# io.net
KiCad netlist of a schematic drawn in EAGLE
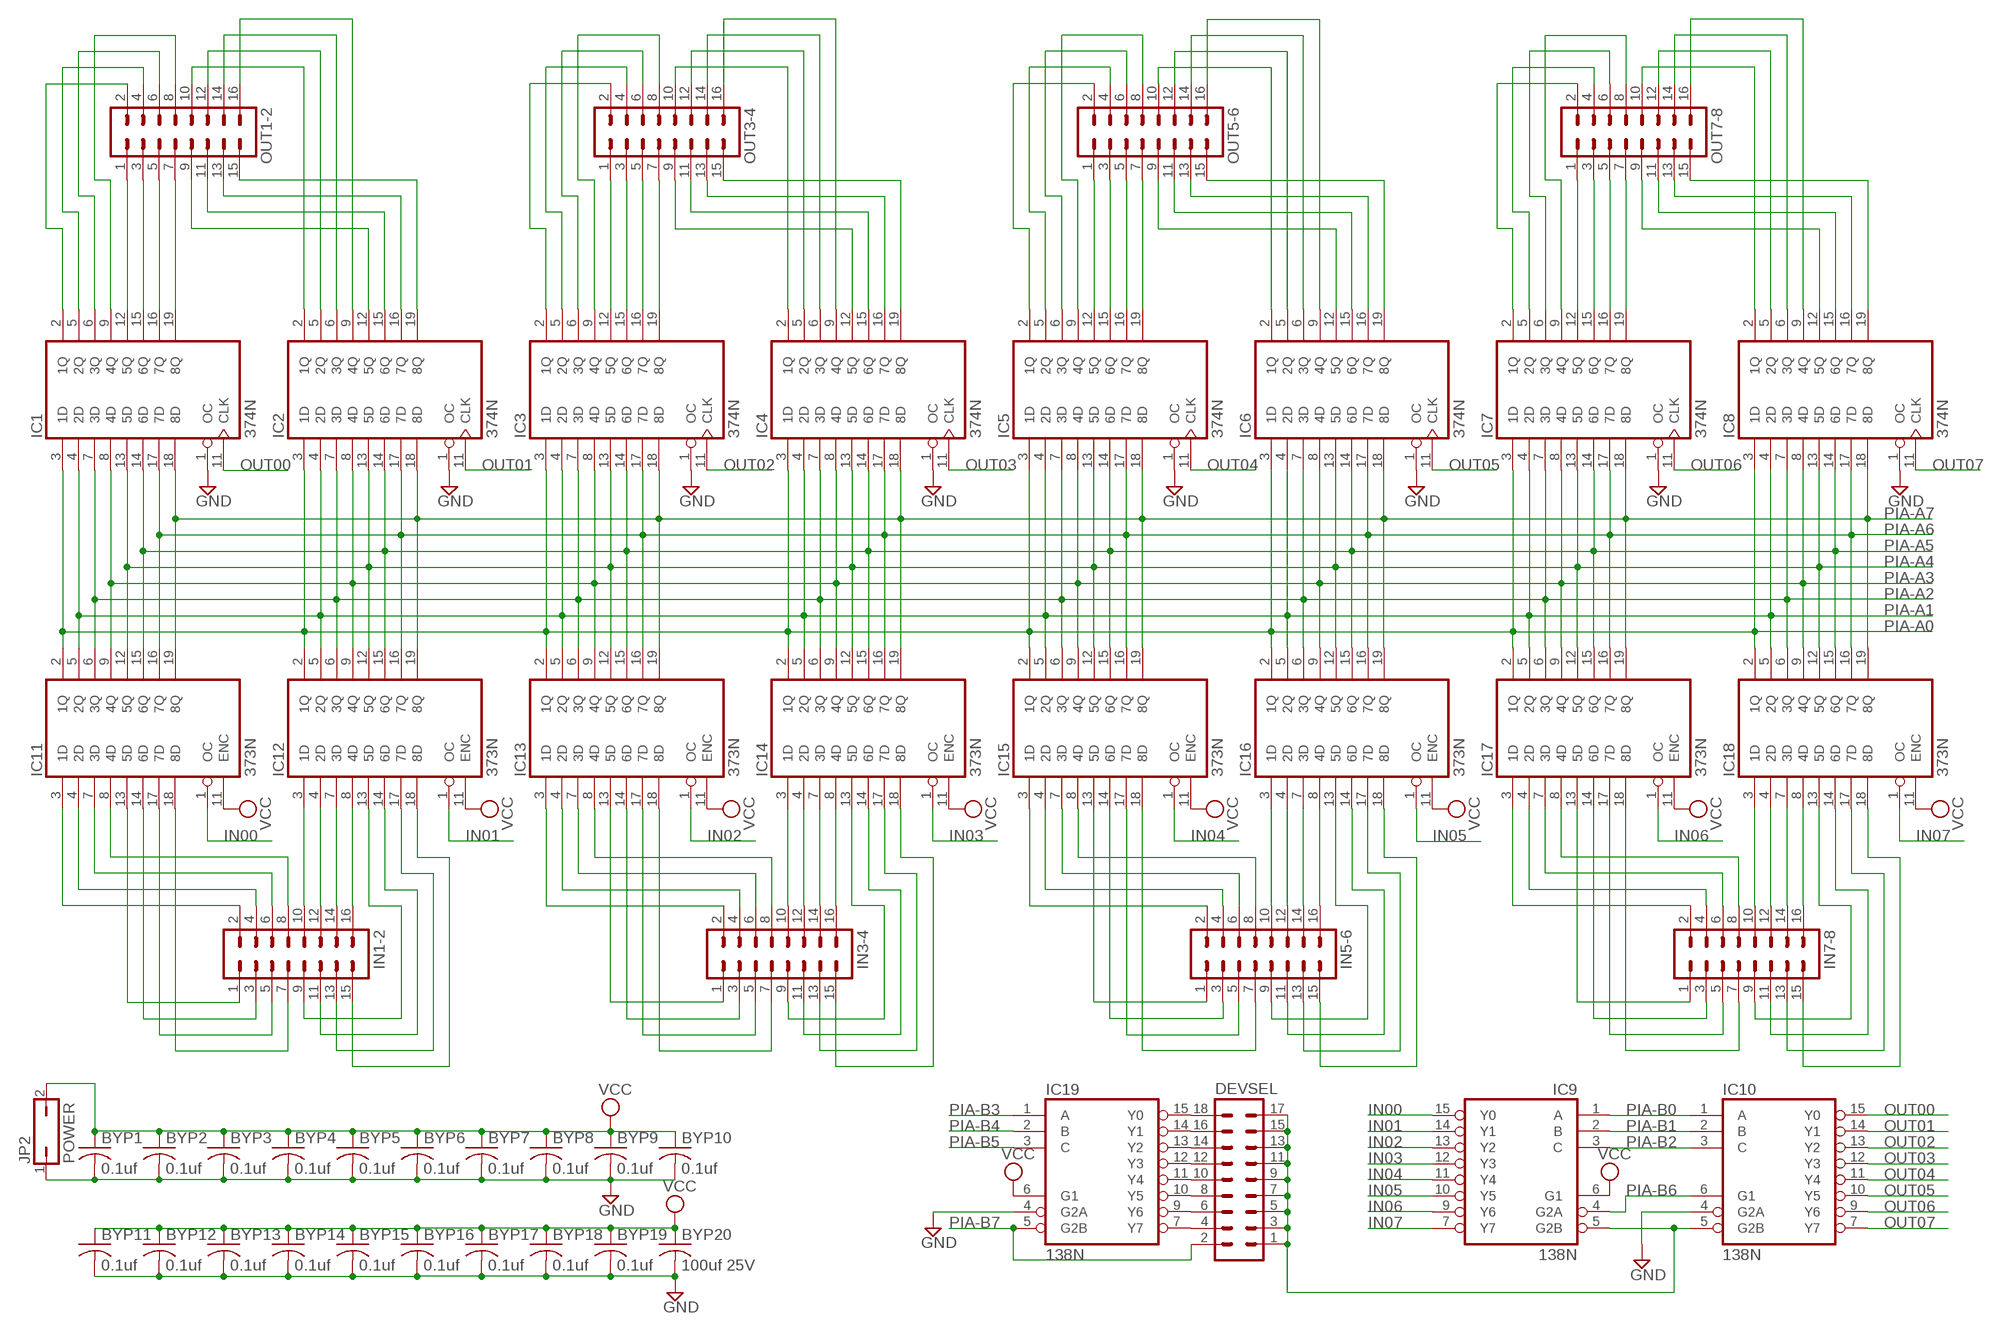
[diagram p0: schematic, sheet 1]
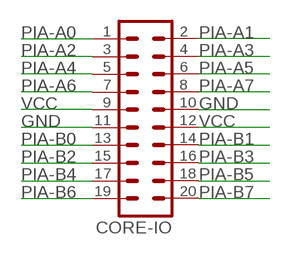
[diagram p1: schematic, sheet 2]

(export (version "E")
  (design (tool "Eeschema 10.0.6"))
  (components
    (comp (ref "BYP1")
      (value "0.1uf")
      (footprint "eagle-import:C050-025X075")
      (libsource (lib "eagle-import") (part "C-US050-025X075"))
    )
    (comp (ref "BYP2")
      (value "0.1uf")
      (footprint "eagle-import:C050-025X075")
      (libsource (lib "eagle-import") (part "C-US050-025X075"))
    )
    (comp (ref "BYP3")
      (value "0.1uf")
      (footprint "eagle-import:C050-025X075")
      (libsource (lib "eagle-import") (part "C-US050-025X075"))
    )
    (comp (ref "BYP4")
      (value "0.1uf")
      (footprint "eagle-import:C050-025X075")
      (libsource (lib "eagle-import") (part "C-US050-025X075"))
    )
    (comp (ref "BYP5")
      (value "0.1uf")
      (footprint "eagle-import:C050-025X075")
      (libsource (lib "eagle-import") (part "C-US050-025X075"))
    )
    (comp (ref "BYP6")
      (value "0.1uf")
      (footprint "eagle-import:C050-025X075")
      (libsource (lib "eagle-import") (part "C-US050-025X075"))
    )
    (comp (ref "BYP7")
      (value "0.1uf")
      (footprint "eagle-import:C050-025X075")
      (libsource (lib "eagle-import") (part "C-US050-025X075"))
    )
    (comp (ref "BYP8")
      (value "0.1uf")
      (footprint "eagle-import:C050-025X075")
      (libsource (lib "eagle-import") (part "C-US050-025X075"))
    )
    (comp (ref "BYP9")
      (value "0.1uf")
      (footprint "eagle-import:C050-025X075")
      (libsource (lib "eagle-import") (part "C-US050-025X075"))
    )
    (comp (ref "BYP10")
      (value "0.1uf")
      (footprint "eagle-import:C050-025X075")
      (libsource (lib "eagle-import") (part "C-US050-025X075"))
    )
    (comp (ref "BYP11")
      (value "0.1uf")
      (footprint "eagle-import:C050-025X075")
      (libsource (lib "eagle-import") (part "C-US050-025X075"))
    )
    (comp (ref "BYP12")
      (value "0.1uf")
      (footprint "eagle-import:C050-025X075")
      (libsource (lib "eagle-import") (part "C-US050-025X075"))
    )
    (comp (ref "BYP13")
      (value "0.1uf")
      (footprint "eagle-import:C050-025X075")
      (libsource (lib "eagle-import") (part "C-US050-025X075"))
    )
    (comp (ref "BYP14")
      (value "0.1uf")
      (footprint "eagle-import:C050-025X075")
      (libsource (lib "eagle-import") (part "C-US050-025X075"))
    )
    (comp (ref "BYP15")
      (value "0.1uf")
      (footprint "eagle-import:C050-025X075")
      (libsource (lib "eagle-import") (part "C-US050-025X075"))
    )
    (comp (ref "BYP16")
      (value "0.1uf")
      (footprint "eagle-import:C050-025X075")
      (libsource (lib "eagle-import") (part "C-US050-025X075"))
    )
    (comp (ref "BYP17")
      (value "0.1uf")
      (footprint "eagle-import:C050-025X075")
      (libsource (lib "eagle-import") (part "C-US050-025X075"))
    )
    (comp (ref "BYP18")
      (value "0.1uf")
      (footprint "eagle-import:C050-025X075")
      (libsource (lib "eagle-import") (part "C-US050-025X075"))
    )
    (comp (ref "BYP19")
      (value "0.1uf")
      (footprint "eagle-import:C050-025X075")
      (libsource (lib "eagle-import") (part "C-US050-025X075"))
    )
    (comp (ref "BYP20")
      (value "100uf 25V")
      (footprint "eagle-import:C150-064X183")
      (libsource (lib "eagle-import") (part "C-US150-064X183"))
    )
    (comp (ref "DEVSEL")
      (value "MA09-2")
      (footprint "eagle-import:MA09-2")
      (libsource (lib "eagle-import") (part "MA09-2"))
    )
    (comp (ref "IC1")
      (value "374N")
      (footprint "eagle-import:DIL20")
      (libsource (lib "eagle-import") (part "74374NLS"))
    )
    (comp (ref "IC2")
      (value "374N")
      (footprint "eagle-import:DIL20")
      (libsource (lib "eagle-import") (part "74374NLS"))
    )
    (comp (ref "IC3")
      (value "374N")
      (footprint "eagle-import:DIL20")
      (libsource (lib "eagle-import") (part "74374NLS"))
    )
    (comp (ref "IC4")
      (value "374N")
      (footprint "eagle-import:DIL20")
      (libsource (lib "eagle-import") (part "74374NLS"))
    )
    (comp (ref "IC5")
      (value "374N")
      (footprint "eagle-import:DIL20")
      (libsource (lib "eagle-import") (part "74374NLS"))
    )
    (comp (ref "IC6")
      (value "374N")
      (footprint "eagle-import:DIL20")
      (libsource (lib "eagle-import") (part "74374NLS"))
    )
    (comp (ref "IC7")
      (value "374N")
      (footprint "eagle-import:DIL20")
      (libsource (lib "eagle-import") (part "74374NLS"))
    )
    (comp (ref "IC8")
      (value "374N")
      (footprint "eagle-import:DIL20")
      (libsource (lib "eagle-import") (part "74374NLS"))
    )
    (comp (ref "IC9")
      (value "138N")
      (footprint "eagle-import:DIL16")
      (libsource (lib "eagle-import") (part "74138NLS"))
    )
    (comp (ref "IC10")
      (value "138N")
      (footprint "eagle-import:DIL16")
      (libsource (lib "eagle-import") (part "74138NLS"))
    )
    (comp (ref "IC11")
      (value "373N")
      (footprint "eagle-import:DIL20")
      (libsource (lib "eagle-import") (part "74373NLS"))
    )
    (comp (ref "IC12")
      (value "373N")
      (footprint "eagle-import:DIL20")
      (libsource (lib "eagle-import") (part "74373NLS"))
    )
    (comp (ref "IC13")
      (value "373N")
      (footprint "eagle-import:DIL20")
      (libsource (lib "eagle-import") (part "74373NLS"))
    )
    (comp (ref "IC14")
      (value "373N")
      (footprint "eagle-import:DIL20")
      (libsource (lib "eagle-import") (part "74373NLS"))
    )
    (comp (ref "IC15")
      (value "373N")
      (footprint "eagle-import:DIL20")
      (libsource (lib "eagle-import") (part "74373NLS"))
    )
    (comp (ref "IC16")
      (value "373N")
      (footprint "eagle-import:DIL20")
      (libsource (lib "eagle-import") (part "74373NLS"))
    )
    (comp (ref "IC17")
      (value "373N")
      (footprint "eagle-import:DIL20")
      (libsource (lib "eagle-import") (part "74373NLS"))
    )
    (comp (ref "IC18")
      (value "373N")
      (footprint "eagle-import:DIL20")
      (libsource (lib "eagle-import") (part "74373NLS"))
    )
    (comp (ref "IC19")
      (value "138N")
      (footprint "eagle-import:DIL16")
      (libsource (lib "eagle-import") (part "74138NLS"))
    )
    (comp (ref "IN1-2")
      (value "MA08-2")
      (footprint "eagle-import:MA08-2")
      (libsource (lib "eagle-import") (part "MA08-2"))
    )
    (comp (ref "IN3-4")
      (value "MA08-2")
      (footprint "eagle-import:MA08-2")
      (libsource (lib "eagle-import") (part "MA08-2"))
    )
    (comp (ref "IN5-6")
      (value "MA08-2")
      (footprint "eagle-import:MA08-2")
      (libsource (lib "eagle-import") (part "MA08-2"))
    )
    (comp (ref "IN7-8")
      (value "MA08-2")
      (footprint "eagle-import:MA08-2")
      (libsource (lib "eagle-import") (part "MA08-2"))
    )
    (comp (ref "JP2")
      (value "POWER")
      (footprint "eagle-import:JP1")
      (libsource (lib "eagle-import") (part "JP1Q"))
    )
    (comp (ref "OUT1-2")
      (value "MA08-2")
      (footprint "eagle-import:MA08-2")
      (libsource (lib "eagle-import") (part "MA08-2"))
    )
    (comp (ref "OUT3-4")
      (value "MA08-2")
      (footprint "eagle-import:MA08-2")
      (libsource (lib "eagle-import") (part "MA08-2"))
    )
    (comp (ref "OUT5-6")
      (value "MA08-2")
      (footprint "eagle-import:MA08-2")
      (libsource (lib "eagle-import") (part "MA08-2"))
    )
    (comp (ref "OUT7-8")
      (value "MA08-2")
      (footprint "eagle-import:MA08-2")
      (libsource (lib "eagle-import") (part "MA08-2"))
    )
    (comp (ref "CORE-IO")
      (value "MA10-2")
      (footprint "eagle-import:MA10-2")
      (libsource (lib "eagle-import") (part "MA10-2"))
    )
  )
  (nets
    (net (code "1") (name "GND") (class "Default")
      (node (ref "BYP1") (pin "2") (pinfunction "2_2") (pintype "passive"))
      (node (ref "BYP10") (pin "2") (pinfunction "2_2") (pintype "passive"))
      (node (ref "BYP11") (pin "2") (pinfunction "2_2") (pintype "passive"))
      (node (ref "BYP12") (pin "2") (pinfunction "2_2") (pintype "passive"))
      (node (ref "BYP13") (pin "2") (pinfunction "2_2") (pintype "passive"))
      (node (ref "BYP14") (pin "2") (pinfunction "2_2") (pintype "passive"))
      (node (ref "BYP15") (pin "2") (pinfunction "2_2") (pintype "passive"))
      (node (ref "BYP16") (pin "2") (pinfunction "2_2") (pintype "passive"))
      (node (ref "BYP17") (pin "2") (pinfunction "2_2") (pintype "passive"))
      (node (ref "BYP18") (pin "2") (pinfunction "2_2") (pintype "passive"))
      (node (ref "BYP19") (pin "2") (pinfunction "2_2") (pintype "passive"))
      (node (ref "BYP2") (pin "2") (pinfunction "2_2") (pintype "passive"))
      (node (ref "BYP20") (pin "2") (pinfunction "2_2") (pintype "passive"))
      (node (ref "BYP3") (pin "2") (pinfunction "2_2") (pintype "passive"))
      (node (ref "BYP4") (pin "2") (pinfunction "2_2") (pintype "passive"))
      (node (ref "BYP5") (pin "2") (pinfunction "2_2") (pintype "passive"))
      (node (ref "BYP6") (pin "2") (pinfunction "2_2") (pintype "passive"))
      (node (ref "BYP7") (pin "2") (pinfunction "2_2") (pintype "passive"))
      (node (ref "BYP8") (pin "2") (pinfunction "2_2") (pintype "passive"))
      (node (ref "BYP9") (pin "2") (pinfunction "2_2") (pintype "passive"))
      (node (ref "CORE-IO") (pin "10") (pinfunction "10_10") (pintype "passive"))
      (node (ref "CORE-IO") (pin "11") (pinfunction "11_11") (pintype "passive"))
      (node (ref "IC1") (pin "1") (pinfunction "OC_1") (pintype "input"))
      (node (ref "IC10") (pin "4") (pinfunction "G2A_4") (pintype "input"))
      (node (ref "IC19") (pin "4") (pinfunction "G2A_4") (pintype "input"))
      (node (ref "IC2") (pin "1") (pinfunction "OC_1") (pintype "input"))
      (node (ref "IC3") (pin "1") (pinfunction "OC_1") (pintype "input"))
      (node (ref "IC4") (pin "1") (pinfunction "OC_1") (pintype "input"))
      (node (ref "IC5") (pin "1") (pinfunction "OC_1") (pintype "input"))
      (node (ref "IC6") (pin "1") (pinfunction "OC_1") (pintype "input"))
      (node (ref "IC7") (pin "1") (pinfunction "OC_1") (pintype "input"))
      (node (ref "IC8") (pin "1") (pinfunction "OC_1") (pintype "input"))
      (node (ref "JP2") (pin "1") (pinfunction "1_1") (pintype "passive"))
    )
    (net (code "2") (name "IN00") (class "Default")
      (node (ref "IC11") (pin "1") (pinfunction "OC_1") (pintype "input"))
      (node (ref "IC9") (pin "15") (pinfunction "Y0_15") (pintype "output"))
    )
    (net (code "3") (name "IN01") (class "Default")
      (node (ref "IC12") (pin "1") (pinfunction "OC_1") (pintype "input"))
      (node (ref "IC9") (pin "14") (pinfunction "Y1_14") (pintype "output"))
    )
    (net (code "4") (name "IN02") (class "Default")
      (node (ref "IC13") (pin "1") (pinfunction "OC_1") (pintype "input"))
      (node (ref "IC9") (pin "13") (pinfunction "Y2_13") (pintype "output"))
    )
    (net (code "5") (name "IN03") (class "Default")
      (node (ref "IC14") (pin "1") (pinfunction "OC_1") (pintype "input"))
      (node (ref "IC9") (pin "12") (pinfunction "Y3_12") (pintype "output"))
    )
    (net (code "6") (name "IN04") (class "Default")
      (node (ref "IC15") (pin "1") (pinfunction "OC_1") (pintype "input"))
      (node (ref "IC9") (pin "11") (pinfunction "Y4_11") (pintype "output"))
    )
    (net (code "7") (name "IN05") (class "Default")
      (node (ref "IC16") (pin "1") (pinfunction "OC_1") (pintype "input"))
      (node (ref "IC9") (pin "10") (pinfunction "Y5_10") (pintype "output"))
    )
    (net (code "8") (name "IN06") (class "Default")
      (node (ref "IC17") (pin "1") (pinfunction "OC_1") (pintype "input"))
      (node (ref "IC9") (pin "9") (pinfunction "Y6_9") (pintype "output"))
    )
    (net (code "9") (name "IN07") (class "Default")
      (node (ref "IC18") (pin "1") (pinfunction "OC_1") (pintype "input"))
      (node (ref "IC9") (pin "7") (pinfunction "Y7_7") (pintype "output"))
    )
    (net (code "10") (name "Net-(IC1A-1Q)") (class "Default")
      (node (ref "IC1") (pin "2") (pinfunction "1Q_2") (pintype "tri_state"))
      (node (ref "OUT1-2") (pin "2") (pinfunction "2_2") (pintype "passive"))
    )
    (net (code "11") (name "Net-(IC1A-2Q)") (class "Default")
      (node (ref "IC1") (pin "5") (pinfunction "2Q_5") (pintype "tri_state"))
      (node (ref "OUT1-2") (pin "4") (pinfunction "4_4") (pintype "passive"))
    )
    (net (code "12") (name "Net-(IC1A-3Q)") (class "Default")
      (node (ref "IC1") (pin "6") (pinfunction "3Q_6") (pintype "tri_state"))
      (node (ref "OUT1-2") (pin "6") (pinfunction "6_6") (pintype "passive"))
    )
    (net (code "13") (name "Net-(IC1A-4Q)") (class "Default")
      (node (ref "IC1") (pin "9") (pinfunction "4Q_9") (pintype "tri_state"))
      (node (ref "OUT1-2") (pin "8") (pinfunction "8_8") (pintype "passive"))
    )
    (net (code "14") (name "Net-(IC1A-5Q)") (class "Default")
      (node (ref "IC1") (pin "12") (pinfunction "5Q_12") (pintype "tri_state"))
      (node (ref "OUT1-2") (pin "1") (pinfunction "1_1") (pintype "passive"))
    )
    (net (code "15") (name "Net-(IC1A-6Q)") (class "Default")
      (node (ref "IC1") (pin "15") (pinfunction "6Q_15") (pintype "tri_state"))
      (node (ref "OUT1-2") (pin "3") (pinfunction "3_3") (pintype "passive"))
    )
    (net (code "16") (name "Net-(IC1A-7Q)") (class "Default")
      (node (ref "IC1") (pin "16") (pinfunction "7Q_16") (pintype "tri_state"))
      (node (ref "OUT1-2") (pin "5") (pinfunction "5_5") (pintype "passive"))
    )
    (net (code "17") (name "Net-(IC1A-8Q)") (class "Default")
      (node (ref "IC1") (pin "19") (pinfunction "8Q_19") (pintype "tri_state"))
      (node (ref "OUT1-2") (pin "7") (pinfunction "7_7") (pintype "passive"))
    )
    (net (code "18") (name "Net-(IC2A-1Q)") (class "Default")
      (node (ref "IC2") (pin "2") (pinfunction "1Q_2") (pintype "tri_state"))
      (node (ref "OUT1-2") (pin "10") (pinfunction "10_10") (pintype "passive"))
    )
    (net (code "19") (name "Net-(IC2A-2Q)") (class "Default")
      (node (ref "IC2") (pin "5") (pinfunction "2Q_5") (pintype "tri_state"))
      (node (ref "OUT1-2") (pin "12") (pinfunction "12_12") (pintype "passive"))
    )
    (net (code "20") (name "Net-(IC2A-3Q)") (class "Default")
      (node (ref "IC2") (pin "6") (pinfunction "3Q_6") (pintype "tri_state"))
      (node (ref "OUT1-2") (pin "14") (pinfunction "14_14") (pintype "passive"))
    )
    (net (code "21") (name "Net-(IC2A-4Q)") (class "Default")
      (node (ref "IC2") (pin "9") (pinfunction "4Q_9") (pintype "tri_state"))
      (node (ref "OUT1-2") (pin "16") (pinfunction "16_16") (pintype "passive"))
    )
    (net (code "22") (name "Net-(IC2A-5Q)") (class "Default")
      (node (ref "IC2") (pin "12") (pinfunction "5Q_12") (pintype "tri_state"))
      (node (ref "OUT1-2") (pin "9") (pinfunction "9_9") (pintype "passive"))
    )
    (net (code "23") (name "Net-(IC2A-6Q)") (class "Default")
      (node (ref "IC2") (pin "15") (pinfunction "6Q_15") (pintype "tri_state"))
      (node (ref "OUT1-2") (pin "11") (pinfunction "11_11") (pintype "passive"))
    )
    (net (code "24") (name "Net-(IC2A-7Q)") (class "Default")
      (node (ref "IC2") (pin "16") (pinfunction "7Q_16") (pintype "tri_state"))
      (node (ref "OUT1-2") (pin "13") (pinfunction "13_13") (pintype "passive"))
    )
    (net (code "25") (name "Net-(IC2A-8Q)") (class "Default")
      (node (ref "IC2") (pin "19") (pinfunction "8Q_19") (pintype "tri_state"))
      (node (ref "OUT1-2") (pin "15") (pinfunction "15_15") (pintype "passive"))
    )
    (net (code "26") (name "Net-(IC3A-1Q)") (class "Default")
      (node (ref "IC3") (pin "2") (pinfunction "1Q_2") (pintype "tri_state"))
      (node (ref "OUT3-4") (pin "2") (pinfunction "2_2") (pintype "passive"))
    )
    (net (code "27") (name "Net-(IC3A-2Q)") (class "Default")
      (node (ref "IC3") (pin "5") (pinfunction "2Q_5") (pintype "tri_state"))
      (node (ref "OUT3-4") (pin "4") (pinfunction "4_4") (pintype "passive"))
    )
    (net (code "28") (name "Net-(IC3A-3Q)") (class "Default")
      (node (ref "IC3") (pin "6") (pinfunction "3Q_6") (pintype "tri_state"))
      (node (ref "OUT3-4") (pin "6") (pinfunction "6_6") (pintype "passive"))
    )
    (net (code "29") (name "Net-(IC3A-4Q)") (class "Default")
      (node (ref "IC3") (pin "9") (pinfunction "4Q_9") (pintype "tri_state"))
      (node (ref "OUT3-4") (pin "8") (pinfunction "8_8") (pintype "passive"))
    )
    (net (code "30") (name "Net-(IC3A-5Q)") (class "Default")
      (node (ref "IC3") (pin "12") (pinfunction "5Q_12") (pintype "tri_state"))
      (node (ref "OUT3-4") (pin "1") (pinfunction "1_1") (pintype "passive"))
    )
    (net (code "31") (name "Net-(IC3A-6Q)") (class "Default")
      (node (ref "IC3") (pin "15") (pinfunction "6Q_15") (pintype "tri_state"))
      (node (ref "OUT3-4") (pin "3") (pinfunction "3_3") (pintype "passive"))
    )
    (net (code "32") (name "Net-(IC3A-7Q)") (class "Default")
      (node (ref "IC3") (pin "16") (pinfunction "7Q_16") (pintype "tri_state"))
      (node (ref "OUT3-4") (pin "5") (pinfunction "5_5") (pintype "passive"))
    )
    (net (code "33") (name "Net-(IC3A-8Q)") (class "Default")
      (node (ref "IC3") (pin "19") (pinfunction "8Q_19") (pintype "tri_state"))
      (node (ref "OUT3-4") (pin "7") (pinfunction "7_7") (pintype "passive"))
    )
    (net (code "34") (name "Net-(IC4A-1Q)") (class "Default")
      (node (ref "IC4") (pin "2") (pinfunction "1Q_2") (pintype "tri_state"))
      (node (ref "OUT3-4") (pin "10") (pinfunction "10_10") (pintype "passive"))
    )
    (net (code "35") (name "Net-(IC4A-2Q)") (class "Default")
      (node (ref "IC4") (pin "5") (pinfunction "2Q_5") (pintype "tri_state"))
      (node (ref "OUT3-4") (pin "12") (pinfunction "12_12") (pintype "passive"))
    )
    (net (code "36") (name "Net-(IC4A-3Q)") (class "Default")
      (node (ref "IC4") (pin "6") (pinfunction "3Q_6") (pintype "tri_state"))
      (node (ref "OUT3-4") (pin "14") (pinfunction "14_14") (pintype "passive"))
    )
    (net (code "37") (name "Net-(IC4A-4Q)") (class "Default")
      (node (ref "IC4") (pin "9") (pinfunction "4Q_9") (pintype "tri_state"))
      (node (ref "OUT3-4") (pin "16") (pinfunction "16_16") (pintype "passive"))
    )
    (net (code "38") (name "Net-(IC4A-5Q)") (class "Default")
      (node (ref "IC4") (pin "12") (pinfunction "5Q_12") (pintype "tri_state"))
      (node (ref "OUT3-4") (pin "9") (pinfunction "9_9") (pintype "passive"))
    )
    (net (code "39") (name "Net-(IC4A-6Q)") (class "Default")
      (node (ref "IC4") (pin "15") (pinfunction "6Q_15") (pintype "tri_state"))
      (node (ref "OUT3-4") (pin "11") (pinfunction "11_11") (pintype "passive"))
    )
    (net (code "40") (name "Net-(IC4A-7Q)") (class "Default")
      (node (ref "IC4") (pin "16") (pinfunction "7Q_16") (pintype "tri_state"))
      (node (ref "OUT3-4") (pin "13") (pinfunction "13_13") (pintype "passive"))
    )
    (net (code "41") (name "Net-(IC4A-8Q)") (class "Default")
      (node (ref "IC4") (pin "19") (pinfunction "8Q_19") (pintype "tri_state"))
      (node (ref "OUT3-4") (pin "15") (pinfunction "15_15") (pintype "passive"))
    )
    (net (code "42") (name "Net-(IC5A-1Q)") (class "Default")
      (node (ref "IC5") (pin "2") (pinfunction "1Q_2") (pintype "tri_state"))
      (node (ref "OUT5-6") (pin "2") (pinfunction "2_2") (pintype "passive"))
    )
    (net (code "43") (name "Net-(IC5A-2Q)") (class "Default")
      (node (ref "IC5") (pin "5") (pinfunction "2Q_5") (pintype "tri_state"))
      (node (ref "OUT5-6") (pin "4") (pinfunction "4_4") (pintype "passive"))
    )
    (net (code "44") (name "Net-(IC5A-3Q)") (class "Default")
      (node (ref "IC5") (pin "6") (pinfunction "3Q_6") (pintype "tri_state"))
      (node (ref "OUT5-6") (pin "6") (pinfunction "6_6") (pintype "passive"))
    )
    (net (code "45") (name "Net-(IC5A-4Q)") (class "Default")
      (node (ref "IC5") (pin "9") (pinfunction "4Q_9") (pintype "tri_state"))
      (node (ref "OUT5-6") (pin "8") (pinfunction "8_8") (pintype "passive"))
    )
    (net (code "46") (name "Net-(IC5A-5Q)") (class "Default")
      (node (ref "IC5") (pin "12") (pinfunction "5Q_12") (pintype "tri_state"))
      (node (ref "OUT5-6") (pin "1") (pinfunction "1_1") (pintype "passive"))
    )
    (net (code "47") (name "Net-(IC5A-6Q)") (class "Default")
      (node (ref "IC5") (pin "15") (pinfunction "6Q_15") (pintype "tri_state"))
      (node (ref "OUT5-6") (pin "3") (pinfunction "3_3") (pintype "passive"))
    )
    (net (code "48") (name "Net-(IC5A-7Q)") (class "Default")
      (node (ref "IC5") (pin "16") (pinfunction "7Q_16") (pintype "tri_state"))
      (node (ref "OUT5-6") (pin "5") (pinfunction "5_5") (pintype "passive"))
    )
    (net (code "49") (name "Net-(IC5A-8Q)") (class "Default")
      (node (ref "IC5") (pin "19") (pinfunction "8Q_19") (pintype "tri_state"))
      (node (ref "OUT5-6") (pin "7") (pinfunction "7_7") (pintype "passive"))
    )
    (net (code "50") (name "Net-(IC6A-1Q)") (class "Default")
      (node (ref "IC6") (pin "2") (pinfunction "1Q_2") (pintype "tri_state"))
      (node (ref "OUT5-6") (pin "10") (pinfunction "10_10") (pintype "passive"))
    )
    (net (code "51") (name "Net-(IC6A-2Q)") (class "Default")
      (node (ref "IC6") (pin "5") (pinfunction "2Q_5") (pintype "tri_state"))
      (node (ref "OUT5-6") (pin "12") (pinfunction "12_12") (pintype "passive"))
    )
    (net (code "52") (name "Net-(IC6A-3Q)") (class "Default")
      (node (ref "IC6") (pin "6") (pinfunction "3Q_6") (pintype "tri_state"))
      (node (ref "OUT5-6") (pin "14") (pinfunction "14_14") (pintype "passive"))
    )
    (net (code "53") (name "Net-(IC6A-4Q)") (class "Default")
      (node (ref "IC6") (pin "9") (pinfunction "4Q_9") (pintype "tri_state"))
      (node (ref "OUT5-6") (pin "16") (pinfunction "16_16") (pintype "passive"))
    )
    (net (code "54") (name "Net-(IC6A-5Q)") (class "Default")
      (node (ref "IC6") (pin "12") (pinfunction "5Q_12") (pintype "tri_state"))
      (node (ref "OUT5-6") (pin "9") (pinfunction "9_9") (pintype "passive"))
    )
    (net (code "55") (name "Net-(IC6A-6Q)") (class "Default")
      (node (ref "IC6") (pin "15") (pinfunction "6Q_15") (pintype "tri_state"))
      (node (ref "OUT5-6") (pin "11") (pinfunction "11_11") (pintype "passive"))
    )
    (net (code "56") (name "Net-(IC6A-7Q)") (class "Default")
      (node (ref "IC6") (pin "16") (pinfunction "7Q_16") (pintype "tri_state"))
      (node (ref "OUT5-6") (pin "13") (pinfunction "13_13") (pintype "passive"))
    )
    (net (code "57") (name "Net-(IC6A-8Q)") (class "Default")
      (node (ref "IC6") (pin "19") (pinfunction "8Q_19") (pintype "tri_state"))
      (node (ref "OUT5-6") (pin "15") (pinfunction "15_15") (pintype "passive"))
    )
    (net (code "58") (name "Net-(IC7A-1Q)") (class "Default")
      (node (ref "IC7") (pin "2") (pinfunction "1Q_2") (pintype "tri_state"))
      (node (ref "OUT7-8") (pin "2") (pinfunction "2_2") (pintype "passive"))
    )
    (net (code "59") (name "Net-(IC7A-2Q)") (class "Default")
      (node (ref "IC7") (pin "5") (pinfunction "2Q_5") (pintype "tri_state"))
      (node (ref "OUT7-8") (pin "4") (pinfunction "4_4") (pintype "passive"))
    )
    (net (code "60") (name "Net-(IC7A-3Q)") (class "Default")
      (node (ref "IC7") (pin "6") (pinfunction "3Q_6") (pintype "tri_state"))
      (node (ref "OUT7-8") (pin "6") (pinfunction "6_6") (pintype "passive"))
    )
    (net (code "61") (name "Net-(IC7A-4Q)") (class "Default")
      (node (ref "IC7") (pin "9") (pinfunction "4Q_9") (pintype "tri_state"))
      (node (ref "OUT7-8") (pin "8") (pinfunction "8_8") (pintype "passive"))
    )
    (net (code "62") (name "Net-(IC7A-5Q)") (class "Default")
      (node (ref "IC7") (pin "12") (pinfunction "5Q_12") (pintype "tri_state"))
      (node (ref "OUT7-8") (pin "1") (pinfunction "1_1") (pintype "passive"))
    )
    (net (code "63") (name "Net-(IC7A-6Q)") (class "Default")
      (node (ref "IC7") (pin "15") (pinfunction "6Q_15") (pintype "tri_state"))
      (node (ref "OUT7-8") (pin "3") (pinfunction "3_3") (pintype "passive"))
    )
    (net (code "64") (name "Net-(IC7A-7Q)") (class "Default")
      (node (ref "IC7") (pin "16") (pinfunction "7Q_16") (pintype "tri_state"))
      (node (ref "OUT7-8") (pin "5") (pinfunction "5_5") (pintype "passive"))
    )
    (net (code "65") (name "Net-(IC7A-8Q)") (class "Default")
      (node (ref "IC7") (pin "19") (pinfunction "8Q_19") (pintype "tri_state"))
      (node (ref "OUT7-8") (pin "7") (pinfunction "7_7") (pintype "passive"))
    )
    (net (code "66") (name "Net-(IC8A-1Q)") (class "Default")
      (node (ref "IC8") (pin "2") (pinfunction "1Q_2") (pintype "tri_state"))
      (node (ref "OUT7-8") (pin "10") (pinfunction "10_10") (pintype "passive"))
    )
    (net (code "67") (name "Net-(IC8A-2Q)") (class "Default")
      (node (ref "IC8") (pin "5") (pinfunction "2Q_5") (pintype "tri_state"))
      (node (ref "OUT7-8") (pin "12") (pinfunction "12_12") (pintype "passive"))
    )
    (net (code "68") (name "Net-(IC8A-3Q)") (class "Default")
      (node (ref "IC8") (pin "6") (pinfunction "3Q_6") (pintype "tri_state"))
      (node (ref "OUT7-8") (pin "14") (pinfunction "14_14") (pintype "passive"))
    )
    (net (code "69") (name "Net-(IC8A-4Q)") (class "Default")
      (node (ref "IC8") (pin "9") (pinfunction "4Q_9") (pintype "tri_state"))
      (node (ref "OUT7-8") (pin "16") (pinfunction "16_16") (pintype "passive"))
    )
    (net (code "70") (name "Net-(IC8A-5Q)") (class "Default")
      (node (ref "IC8") (pin "12") (pinfunction "5Q_12") (pintype "tri_state"))
      (node (ref "OUT7-8") (pin "9") (pinfunction "9_9") (pintype "passive"))
    )
    (net (code "71") (name "Net-(IC8A-6Q)") (class "Default")
      (node (ref "IC8") (pin "15") (pinfunction "6Q_15") (pintype "tri_state"))
      (node (ref "OUT7-8") (pin "11") (pinfunction "11_11") (pintype "passive"))
    )
    (net (code "72") (name "Net-(IC8A-7Q)") (class "Default")
      (node (ref "IC8") (pin "16") (pinfunction "7Q_16") (pintype "tri_state"))
      (node (ref "OUT7-8") (pin "13") (pinfunction "13_13") (pintype "passive"))
    )
    (net (code "73") (name "Net-(IC8A-8Q)") (class "Default")
      (node (ref "IC8") (pin "19") (pinfunction "8Q_19") (pintype "tri_state"))
      (node (ref "OUT7-8") (pin "15") (pinfunction "15_15") (pintype "passive"))
    )
    (net (code "74") (name "Net-(IC10A-G2B)") (class "Default")
      (node (ref "DEVSEL") (pin "1") (pinfunction "1_1") (pintype "passive"))
      (node (ref "DEVSEL") (pin "11") (pinfunction "11_11") (pintype "passive"))
      (node (ref "DEVSEL") (pin "13") (pinfunction "13_13") (pintype "passive"))
      (node (ref "DEVSEL") (pin "15") (pinfunction "15_15") (pintype "passive"))
      (node (ref "DEVSEL") (pin "17") (pinfunction "17_17") (pintype "passive"))
      (node (ref "DEVSEL") (pin "3") (pinfunction "3_3") (pintype "passive"))
      (node (ref "DEVSEL") (pin "5") (pinfunction "5_5") (pintype "passive"))
      (node (ref "DEVSEL") (pin "7") (pinfunction "7_7") (pintype "passive"))
      (node (ref "DEVSEL") (pin "9") (pinfunction "9_9") (pintype "passive"))
      (node (ref "IC10") (pin "5") (pinfunction "G2B_5") (pintype "input"))
      (node (ref "IC9") (pin "5") (pinfunction "G2B_5") (pintype "input"))
    )
    (net (code "75") (name "Net-(IC11A-1D)") (class "Default")
      (node (ref "IC11") (pin "3") (pinfunction "1D_3") (pintype "input"))
      (node (ref "IN1-2") (pin "2") (pinfunction "2_2") (pintype "passive"))
    )
    (net (code "76") (name "Net-(IC11A-2D)") (class "Default")
      (node (ref "IC11") (pin "4") (pinfunction "2D_4") (pintype "input"))
      (node (ref "IN1-2") (pin "4") (pinfunction "4_4") (pintype "passive"))
    )
    (net (code "77") (name "Net-(IC11A-3D)") (class "Default")
      (node (ref "IC11") (pin "7") (pinfunction "3D_7") (pintype "input"))
      (node (ref "IN1-2") (pin "6") (pinfunction "6_6") (pintype "passive"))
    )
    (net (code "78") (name "Net-(IC11A-4D)") (class "Default")
      (node (ref "IC11") (pin "8") (pinfunction "4D_8") (pintype "input"))
      (node (ref "IN1-2") (pin "8") (pinfunction "8_8") (pintype "passive"))
    )
    (net (code "79") (name "Net-(IC11A-5D)") (class "Default")
      (node (ref "IC11") (pin "13") (pinfunction "5D_13") (pintype "input"))
      (node (ref "IN1-2") (pin "1") (pinfunction "1_1") (pintype "passive"))
    )
    (net (code "80") (name "Net-(IC11A-6D)") (class "Default")
      (node (ref "IC11") (pin "14") (pinfunction "6D_14") (pintype "input"))
      (node (ref "IN1-2") (pin "3") (pinfunction "3_3") (pintype "passive"))
    )
    (net (code "81") (name "Net-(IC11A-7D)") (class "Default")
      (node (ref "IC11") (pin "17") (pinfunction "7D_17") (pintype "input"))
      (node (ref "IN1-2") (pin "5") (pinfunction "5_5") (pintype "passive"))
    )
    (net (code "82") (name "Net-(IC11A-8D)") (class "Default")
      (node (ref "IC11") (pin "18") (pinfunction "8D_18") (pintype "input"))
      (node (ref "IN1-2") (pin "7") (pinfunction "7_7") (pintype "passive"))
    )
    (net (code "83") (name "Net-(IC12A-1D)") (class "Default")
      (node (ref "IC12") (pin "3") (pinfunction "1D_3") (pintype "input"))
      (node (ref "IN1-2") (pin "10") (pinfunction "10_10") (pintype "passive"))
    )
    (net (code "84") (name "Net-(IC12A-2D)") (class "Default")
      (node (ref "IC12") (pin "4") (pinfunction "2D_4") (pintype "input"))
      (node (ref "IN1-2") (pin "12") (pinfunction "12_12") (pintype "passive"))
    )
    (net (code "85") (name "Net-(IC12A-3D)") (class "Default")
      (node (ref "IC12") (pin "7") (pinfunction "3D_7") (pintype "input"))
      (node (ref "IN1-2") (pin "14") (pinfunction "14_14") (pintype "passive"))
    )
    (net (code "86") (name "Net-(IC12A-4D)") (class "Default")
      (node (ref "IC12") (pin "8") (pinfunction "4D_8") (pintype "input"))
      (node (ref "IN1-2") (pin "16") (pinfunction "16_16") (pintype "passive"))
    )
    (net (code "87") (name "Net-(IC12A-5D)") (class "Default")
      (node (ref "IC12") (pin "13") (pinfunction "5D_13") (pintype "input"))
      (node (ref "IN1-2") (pin "9") (pinfunction "9_9") (pintype "passive"))
    )
    (net (code "88") (name "Net-(IC12A-6D)") (class "Default")
      (node (ref "IC12") (pin "14") (pinfunction "6D_14") (pintype "input"))
      (node (ref "IN1-2") (pin "11") (pinfunction "11_11") (pintype "passive"))
    )
    (net (code "89") (name "Net-(IC12A-7D)") (class "Default")
      (node (ref "IC12") (pin "17") (pinfunction "7D_17") (pintype "input"))
      (node (ref "IN1-2") (pin "13") (pinfunction "13_13") (pintype "passive"))
    )
    (net (code "90") (name "Net-(IC12A-8D)") (class "Default")
      (node (ref "IC12") (pin "18") (pinfunction "8D_18") (pintype "input"))
      (node (ref "IN1-2") (pin "15") (pinfunction "15_15") (pintype "passive"))
    )
    (net (code "91") (name "Net-(IC13A-1D)") (class "Default")
      (node (ref "IC13") (pin "3") (pinfunction "1D_3") (pintype "input"))
      (node (ref "IN3-4") (pin "2") (pinfunction "2_2") (pintype "passive"))
    )
    (net (code "92") (name "Net-(IC13A-2D)") (class "Default")
      (node (ref "IC13") (pin "4") (pinfunction "2D_4") (pintype "input"))
      (node (ref "IN3-4") (pin "4") (pinfunction "4_4") (pintype "passive"))
    )
    (net (code "93") (name "Net-(IC13A-3D)") (class "Default")
      (node (ref "IC13") (pin "7") (pinfunction "3D_7") (pintype "input"))
      (node (ref "IN3-4") (pin "6") (pinfunction "6_6") (pintype "passive"))
    )
    (net (code "94") (name "Net-(IC13A-4D)") (class "Default")
      (node (ref "IC13") (pin "8") (pinfunction "4D_8") (pintype "input"))
      (node (ref "IN3-4") (pin "8") (pinfunction "8_8") (pintype "passive"))
    )
    (net (code "95") (name "Net-(IC13A-5D)") (class "Default")
      (node (ref "IC13") (pin "13") (pinfunction "5D_13") (pintype "input"))
      (node (ref "IN3-4") (pin "1") (pinfunction "1_1") (pintype "passive"))
    )
    (net (code "96") (name "Net-(IC13A-6D)") (class "Default")
      (node (ref "IC13") (pin "14") (pinfunction "6D_14") (pintype "input"))
      (node (ref "IN3-4") (pin "3") (pinfunction "3_3") (pintype "passive"))
    )
    (net (code "97") (name "Net-(IC13A-7D)") (class "Default")
      (node (ref "IC13") (pin "17") (pinfunction "7D_17") (pintype "input"))
      (node (ref "IN3-4") (pin "5") (pinfunction "5_5") (pintype "passive"))
    )
    (net (code "98") (name "Net-(IC13A-8D)") (class "Default")
      (node (ref "IC13") (pin "18") (pinfunction "8D_18") (pintype "input"))
      (node (ref "IN3-4") (pin "7") (pinfunction "7_7") (pintype "passive"))
    )
    (net (code "99") (name "Net-(IC14A-1D)") (class "Default")
      (node (ref "IC14") (pin "3") (pinfunction "1D_3") (pintype "input"))
      (node (ref "IN3-4") (pin "10") (pinfunction "10_10") (pintype "passive"))
    )
    (net (code "100") (name "Net-(IC14A-2D)") (class "Default")
      (node (ref "IC14") (pin "4") (pinfunction "2D_4") (pintype "input"))
      (node (ref "IN3-4") (pin "12") (pinfunction "12_12") (pintype "passive"))
    )
    (net (code "101") (name "Net-(IC14A-3D)") (class "Default")
      (node (ref "IC14") (pin "7") (pinfunction "3D_7") (pintype "input"))
      (node (ref "IN3-4") (pin "14") (pinfunction "14_14") (pintype "passive"))
    )
    (net (code "102") (name "Net-(IC14A-4D)") (class "Default")
      (node (ref "IC14") (pin "8") (pinfunction "4D_8") (pintype "input"))
      (node (ref "IN3-4") (pin "16") (pinfunction "16_16") (pintype "passive"))
    )
    (net (code "103") (name "Net-(IC14A-5D)") (class "Default")
      (node (ref "IC14") (pin "13") (pinfunction "5D_13") (pintype "input"))
      (node (ref "IN3-4") (pin "9") (pinfunction "9_9") (pintype "passive"))
    )
    (net (code "104") (name "Net-(IC14A-6D)") (class "Default")
      (node (ref "IC14") (pin "14") (pinfunction "6D_14") (pintype "input"))
      (node (ref "IN3-4") (pin "11") (pinfunction "11_11") (pintype "passive"))
    )
    (net (code "105") (name "Net-(IC14A-7D)") (class "Default")
      (node (ref "IC14") (pin "17") (pinfunction "7D_17") (pintype "input"))
      (node (ref "IN3-4") (pin "13") (pinfunction "13_13") (pintype "passive"))
    )
    (net (code "106") (name "Net-(IC14A-8D)") (class "Default")
      (node (ref "IC14") (pin "18") (pinfunction "8D_18") (pintype "input"))
      (node (ref "IN3-4") (pin "15") (pinfunction "15_15") (pintype "passive"))
    )
    (net (code "107") (name "Net-(IC15A-1D)") (class "Default")
      (node (ref "IC15") (pin "3") (pinfunction "1D_3") (pintype "input"))
      (node (ref "IN5-6") (pin "2") (pinfunction "2_2") (pintype "passive"))
    )
    (net (code "108") (name "Net-(IC15A-2D)") (class "Default")
      (node (ref "IC15") (pin "4") (pinfunction "2D_4") (pintype "input"))
      (node (ref "IN5-6") (pin "4") (pinfunction "4_4") (pintype "passive"))
    )
    (net (code "109") (name "Net-(IC15A-3D)") (class "Default")
      (node (ref "IC15") (pin "7") (pinfunction "3D_7") (pintype "input"))
      (node (ref "IN5-6") (pin "6") (pinfunction "6_6") (pintype "passive"))
    )
    (net (code "110") (name "Net-(IC15A-4D)") (class "Default")
      (node (ref "IC15") (pin "8") (pinfunction "4D_8") (pintype "input"))
      (node (ref "IN5-6") (pin "8") (pinfunction "8_8") (pintype "passive"))
    )
    (net (code "111") (name "Net-(IC15A-5D)") (class "Default")
      (node (ref "IC15") (pin "13") (pinfunction "5D_13") (pintype "input"))
      (node (ref "IN5-6") (pin "1") (pinfunction "1_1") (pintype "passive"))
    )
    (net (code "112") (name "Net-(IC15A-6D)") (class "Default")
      (node (ref "IC15") (pin "14") (pinfunction "6D_14") (pintype "input"))
      (node (ref "IN5-6") (pin "3") (pinfunction "3_3") (pintype "passive"))
    )
    (net (code "113") (name "Net-(IC15A-7D)") (class "Default")
      (node (ref "IC15") (pin "17") (pinfunction "7D_17") (pintype "input"))
      (node (ref "IN5-6") (pin "5") (pinfunction "5_5") (pintype "passive"))
    )
    (net (code "114") (name "Net-(IC15A-8D)") (class "Default")
      (node (ref "IC15") (pin "18") (pinfunction "8D_18") (pintype "input"))
      (node (ref "IN5-6") (pin "7") (pinfunction "7_7") (pintype "passive"))
    )
    (net (code "115") (name "Net-(IC16A-1D)") (class "Default")
      (node (ref "IC16") (pin "3") (pinfunction "1D_3") (pintype "input"))
      (node (ref "IN5-6") (pin "10") (pinfunction "10_10") (pintype "passive"))
    )
    (net (code "116") (name "Net-(IC16A-2D)") (class "Default")
      (node (ref "IC16") (pin "4") (pinfunction "2D_4") (pintype "input"))
      (node (ref "IN5-6") (pin "12") (pinfunction "12_12") (pintype "passive"))
    )
    (net (code "117") (name "Net-(IC16A-3D)") (class "Default")
      (node (ref "IC16") (pin "7") (pinfunction "3D_7") (pintype "input"))
      (node (ref "IN5-6") (pin "14") (pinfunction "14_14") (pintype "passive"))
    )
    (net (code "118") (name "Net-(IC16A-4D)") (class "Default")
      (node (ref "IC16") (pin "8") (pinfunction "4D_8") (pintype "input"))
      (node (ref "IN5-6") (pin "16") (pinfunction "16_16") (pintype "passive"))
    )
    (net (code "119") (name "Net-(IC16A-5D)") (class "Default")
      (node (ref "IC16") (pin "13") (pinfunction "5D_13") (pintype "input"))
      (node (ref "IN5-6") (pin "9") (pinfunction "9_9") (pintype "passive"))
    )
    (net (code "120") (name "Net-(IC16A-6D)") (class "Default")
      (node (ref "IC16") (pin "14") (pinfunction "6D_14") (pintype "input"))
      (node (ref "IN5-6") (pin "11") (pinfunction "11_11") (pintype "passive"))
    )
    (net (code "121") (name "Net-(IC16A-7D)") (class "Default")
      (node (ref "IC16") (pin "17") (pinfunction "7D_17") (pintype "input"))
      (node (ref "IN5-6") (pin "13") (pinfunction "13_13") (pintype "passive"))
    )
    (net (code "122") (name "Net-(IC16A-8D)") (class "Default")
      (node (ref "IC16") (pin "18") (pinfunction "8D_18") (pintype "input"))
      (node (ref "IN5-6") (pin "15") (pinfunction "15_15") (pintype "passive"))
    )
    (net (code "123") (name "Net-(IC17A-1D)") (class "Default")
      (node (ref "IC17") (pin "3") (pinfunction "1D_3") (pintype "input"))
      (node (ref "IN7-8") (pin "2") (pinfunction "2_2") (pintype "passive"))
    )
    (net (code "124") (name "Net-(IC17A-2D)") (class "Default")
      (node (ref "IC17") (pin "4") (pinfunction "2D_4") (pintype "input"))
      (node (ref "IN7-8") (pin "4") (pinfunction "4_4") (pintype "passive"))
    )
    (net (code "125") (name "Net-(IC17A-3D)") (class "Default")
      (node (ref "IC17") (pin "7") (pinfunction "3D_7") (pintype "input"))
      (node (ref "IN7-8") (pin "6") (pinfunction "6_6") (pintype "passive"))
    )
    (net (code "126") (name "Net-(IC17A-4D)") (class "Default")
      (node (ref "IC17") (pin "8") (pinfunction "4D_8") (pintype "input"))
      (node (ref "IN7-8") (pin "8") (pinfunction "8_8") (pintype "passive"))
    )
    (net (code "127") (name "Net-(IC17A-5D)") (class "Default")
      (node (ref "IC17") (pin "13") (pinfunction "5D_13") (pintype "input"))
      (node (ref "IN7-8") (pin "1") (pinfunction "1_1") (pintype "passive"))
    )
    (net (code "128") (name "Net-(IC17A-6D)") (class "Default")
      (node (ref "IC17") (pin "14") (pinfunction "6D_14") (pintype "input"))
      (node (ref "IN7-8") (pin "3") (pinfunction "3_3") (pintype "passive"))
    )
    (net (code "129") (name "Net-(IC17A-7D)") (class "Default")
      (node (ref "IC17") (pin "17") (pinfunction "7D_17") (pintype "input"))
      (node (ref "IN7-8") (pin "5") (pinfunction "5_5") (pintype "passive"))
    )
    (net (code "130") (name "Net-(IC17A-8D)") (class "Default")
      (node (ref "IC17") (pin "18") (pinfunction "8D_18") (pintype "input"))
      (node (ref "IN7-8") (pin "7") (pinfunction "7_7") (pintype "passive"))
    )
    (net (code "131") (name "Net-(IC18A-1D)") (class "Default")
      (node (ref "IC18") (pin "3") (pinfunction "1D_3") (pintype "input"))
      (node (ref "IN7-8") (pin "10") (pinfunction "10_10") (pintype "passive"))
    )
    (net (code "132") (name "Net-(IC18A-2D)") (class "Default")
      (node (ref "IC18") (pin "4") (pinfunction "2D_4") (pintype "input"))
      (node (ref "IN7-8") (pin "12") (pinfunction "12_12") (pintype "passive"))
    )
    (net (code "133") (name "Net-(IC18A-3D)") (class "Default")
      (node (ref "IC18") (pin "7") (pinfunction "3D_7") (pintype "input"))
      (node (ref "IN7-8") (pin "14") (pinfunction "14_14") (pintype "passive"))
    )
    (net (code "134") (name "Net-(IC18A-4D)") (class "Default")
      (node (ref "IC18") (pin "8") (pinfunction "4D_8") (pintype "input"))
      (node (ref "IN7-8") (pin "16") (pinfunction "16_16") (pintype "passive"))
    )
    (net (code "135") (name "Net-(IC18A-5D)") (class "Default")
      (node (ref "IC18") (pin "13") (pinfunction "5D_13") (pintype "input"))
      (node (ref "IN7-8") (pin "9") (pinfunction "9_9") (pintype "passive"))
    )
    (net (code "136") (name "Net-(IC18A-6D)") (class "Default")
      (node (ref "IC18") (pin "14") (pinfunction "6D_14") (pintype "input"))
      (node (ref "IN7-8") (pin "11") (pinfunction "11_11") (pintype "passive"))
    )
    (net (code "137") (name "Net-(IC18A-7D)") (class "Default")
      (node (ref "IC18") (pin "17") (pinfunction "7D_17") (pintype "input"))
      (node (ref "IN7-8") (pin "13") (pinfunction "13_13") (pintype "passive"))
    )
    (net (code "138") (name "Net-(IC18A-8D)") (class "Default")
      (node (ref "IC18") (pin "18") (pinfunction "8D_18") (pintype "input"))
      (node (ref "IN7-8") (pin "15") (pinfunction "15_15") (pintype "passive"))
    )
    (net (code "139") (name "Net-(IC19A-Y0)") (class "Default")
      (node (ref "DEVSEL") (pin "18") (pinfunction "18_18") (pintype "passive"))
      (node (ref "IC19") (pin "15") (pinfunction "Y0_15") (pintype "output"))
    )
    (net (code "140") (name "Net-(IC19A-Y1)") (class "Default")
      (node (ref "DEVSEL") (pin "16") (pinfunction "16_16") (pintype "passive"))
      (node (ref "IC19") (pin "14") (pinfunction "Y1_14") (pintype "output"))
    )
    (net (code "141") (name "Net-(IC19A-Y2)") (class "Default")
      (node (ref "DEVSEL") (pin "14") (pinfunction "14_14") (pintype "passive"))
      (node (ref "IC19") (pin "13") (pinfunction "Y2_13") (pintype "output"))
    )
    (net (code "142") (name "Net-(IC19A-Y3)") (class "Default")
      (node (ref "DEVSEL") (pin "12") (pinfunction "12_12") (pintype "passive"))
      (node (ref "IC19") (pin "12") (pinfunction "Y3_12") (pintype "output"))
    )
    (net (code "143") (name "Net-(IC19A-Y4)") (class "Default")
      (node (ref "DEVSEL") (pin "10") (pinfunction "10_10") (pintype "passive"))
      (node (ref "IC19") (pin "11") (pinfunction "Y4_11") (pintype "output"))
    )
    (net (code "144") (name "Net-(IC19A-Y5)") (class "Default")
      (node (ref "DEVSEL") (pin "8") (pinfunction "8_8") (pintype "passive"))
      (node (ref "IC19") (pin "10") (pinfunction "Y5_10") (pintype "output"))
    )
    (net (code "145") (name "Net-(IC19A-Y6)") (class "Default")
      (node (ref "DEVSEL") (pin "6") (pinfunction "6_6") (pintype "passive"))
      (node (ref "IC19") (pin "9") (pinfunction "Y6_9") (pintype "output"))
    )
    (net (code "146") (name "Net-(IC19A-Y7)") (class "Default")
      (node (ref "DEVSEL") (pin "4") (pinfunction "4_4") (pintype "passive"))
      (node (ref "IC19") (pin "7") (pinfunction "Y7_7") (pintype "output"))
    )
    (net (code "147") (name "OUT00") (class "Default")
      (node (ref "IC1") (pin "11") (pinfunction "CLK_11") (pintype "input"))
      (node (ref "IC10") (pin "15") (pinfunction "Y0_15") (pintype "output"))
    )
    (net (code "148") (name "OUT01") (class "Default")
      (node (ref "IC10") (pin "14") (pinfunction "Y1_14") (pintype "output"))
      (node (ref "IC2") (pin "11") (pinfunction "CLK_11") (pintype "input"))
    )
    (net (code "149") (name "OUT02") (class "Default")
      (node (ref "IC10") (pin "13") (pinfunction "Y2_13") (pintype "output"))
      (node (ref "IC3") (pin "11") (pinfunction "CLK_11") (pintype "input"))
    )
    (net (code "150") (name "OUT03") (class "Default")
      (node (ref "IC10") (pin "12") (pinfunction "Y3_12") (pintype "output"))
      (node (ref "IC4") (pin "11") (pinfunction "CLK_11") (pintype "input"))
    )
    (net (code "151") (name "OUT04") (class "Default")
      (node (ref "IC10") (pin "11") (pinfunction "Y4_11") (pintype "output"))
      (node (ref "IC5") (pin "11") (pinfunction "CLK_11") (pintype "input"))
    )
    (net (code "152") (name "OUT05") (class "Default")
      (node (ref "IC10") (pin "10") (pinfunction "Y5_10") (pintype "output"))
      (node (ref "IC6") (pin "11") (pinfunction "CLK_11") (pintype "input"))
    )
    (net (code "153") (name "OUT06") (class "Default")
      (node (ref "IC10") (pin "9") (pinfunction "Y6_9") (pintype "output"))
      (node (ref "IC7") (pin "11") (pinfunction "CLK_11") (pintype "input"))
    )
    (net (code "154") (name "OUT07") (class "Default")
      (node (ref "IC10") (pin "7") (pinfunction "Y7_7") (pintype "output"))
      (node (ref "IC8") (pin "11") (pinfunction "CLK_11") (pintype "input"))
    )
    (net (code "155") (name "PIA-A0") (class "Default")
      (node (ref "CORE-IO") (pin "1") (pinfunction "1_1") (pintype "passive"))
      (node (ref "IC1") (pin "3") (pinfunction "1D_3") (pintype "input"))
      (node (ref "IC11") (pin "2") (pinfunction "1Q_2") (pintype "tri_state"))
      (node (ref "IC12") (pin "2") (pinfunction "1Q_2") (pintype "tri_state"))
      (node (ref "IC13") (pin "2") (pinfunction "1Q_2") (pintype "tri_state"))
      (node (ref "IC14") (pin "2") (pinfunction "1Q_2") (pintype "tri_state"))
      (node (ref "IC15") (pin "2") (pinfunction "1Q_2") (pintype "tri_state"))
      (node (ref "IC16") (pin "2") (pinfunction "1Q_2") (pintype "tri_state"))
      (node (ref "IC17") (pin "2") (pinfunction "1Q_2") (pintype "tri_state"))
      (node (ref "IC18") (pin "2") (pinfunction "1Q_2") (pintype "tri_state"))
      (node (ref "IC2") (pin "3") (pinfunction "1D_3") (pintype "input"))
      (node (ref "IC3") (pin "3") (pinfunction "1D_3") (pintype "input"))
      (node (ref "IC4") (pin "3") (pinfunction "1D_3") (pintype "input"))
      (node (ref "IC5") (pin "3") (pinfunction "1D_3") (pintype "input"))
      (node (ref "IC6") (pin "3") (pinfunction "1D_3") (pintype "input"))
      (node (ref "IC7") (pin "3") (pinfunction "1D_3") (pintype "input"))
      (node (ref "IC8") (pin "3") (pinfunction "1D_3") (pintype "input"))
    )
    (net (code "156") (name "PIA-A1") (class "Default")
      (node (ref "CORE-IO") (pin "2") (pinfunction "2_2") (pintype "passive"))
      (node (ref "IC1") (pin "4") (pinfunction "2D_4") (pintype "input"))
      (node (ref "IC11") (pin "5") (pinfunction "2Q_5") (pintype "tri_state"))
      (node (ref "IC12") (pin "5") (pinfunction "2Q_5") (pintype "tri_state"))
      (node (ref "IC13") (pin "5") (pinfunction "2Q_5") (pintype "tri_state"))
      (node (ref "IC14") (pin "5") (pinfunction "2Q_5") (pintype "tri_state"))
      (node (ref "IC15") (pin "5") (pinfunction "2Q_5") (pintype "tri_state"))
      (node (ref "IC16") (pin "5") (pinfunction "2Q_5") (pintype "tri_state"))
      (node (ref "IC17") (pin "5") (pinfunction "2Q_5") (pintype "tri_state"))
      (node (ref "IC18") (pin "5") (pinfunction "2Q_5") (pintype "tri_state"))
      (node (ref "IC2") (pin "4") (pinfunction "2D_4") (pintype "input"))
      (node (ref "IC3") (pin "4") (pinfunction "2D_4") (pintype "input"))
      (node (ref "IC4") (pin "4") (pinfunction "2D_4") (pintype "input"))
      (node (ref "IC5") (pin "4") (pinfunction "2D_4") (pintype "input"))
      (node (ref "IC6") (pin "4") (pinfunction "2D_4") (pintype "input"))
      (node (ref "IC7") (pin "4") (pinfunction "2D_4") (pintype "input"))
      (node (ref "IC8") (pin "4") (pinfunction "2D_4") (pintype "input"))
    )
    (net (code "157") (name "PIA-A2") (class "Default")
      (node (ref "CORE-IO") (pin "3") (pinfunction "3_3") (pintype "passive"))
      (node (ref "IC1") (pin "7") (pinfunction "3D_7") (pintype "input"))
      (node (ref "IC11") (pin "6") (pinfunction "3Q_6") (pintype "tri_state"))
      (node (ref "IC12") (pin "6") (pinfunction "3Q_6") (pintype "tri_state"))
      (node (ref "IC13") (pin "6") (pinfunction "3Q_6") (pintype "tri_state"))
      (node (ref "IC14") (pin "6") (pinfunction "3Q_6") (pintype "tri_state"))
      (node (ref "IC15") (pin "6") (pinfunction "3Q_6") (pintype "tri_state"))
      (node (ref "IC16") (pin "6") (pinfunction "3Q_6") (pintype "tri_state"))
      (node (ref "IC17") (pin "6") (pinfunction "3Q_6") (pintype "tri_state"))
      (node (ref "IC18") (pin "6") (pinfunction "3Q_6") (pintype "tri_state"))
      (node (ref "IC2") (pin "7") (pinfunction "3D_7") (pintype "input"))
      (node (ref "IC3") (pin "7") (pinfunction "3D_7") (pintype "input"))
      (node (ref "IC4") (pin "7") (pinfunction "3D_7") (pintype "input"))
      (node (ref "IC5") (pin "7") (pinfunction "3D_7") (pintype "input"))
      (node (ref "IC6") (pin "7") (pinfunction "3D_7") (pintype "input"))
      (node (ref "IC7") (pin "7") (pinfunction "3D_7") (pintype "input"))
      (node (ref "IC8") (pin "7") (pinfunction "3D_7") (pintype "input"))
    )
    (net (code "158") (name "PIA-A3") (class "Default")
      (node (ref "CORE-IO") (pin "4") (pinfunction "4_4") (pintype "passive"))
      (node (ref "IC1") (pin "8") (pinfunction "4D_8") (pintype "input"))
      (node (ref "IC11") (pin "9") (pinfunction "4Q_9") (pintype "tri_state"))
      (node (ref "IC12") (pin "9") (pinfunction "4Q_9") (pintype "tri_state"))
      (node (ref "IC13") (pin "9") (pinfunction "4Q_9") (pintype "tri_state"))
      (node (ref "IC14") (pin "9") (pinfunction "4Q_9") (pintype "tri_state"))
      (node (ref "IC15") (pin "9") (pinfunction "4Q_9") (pintype "tri_state"))
      (node (ref "IC16") (pin "9") (pinfunction "4Q_9") (pintype "tri_state"))
      (node (ref "IC17") (pin "9") (pinfunction "4Q_9") (pintype "tri_state"))
      (node (ref "IC18") (pin "9") (pinfunction "4Q_9") (pintype "tri_state"))
      (node (ref "IC2") (pin "8") (pinfunction "4D_8") (pintype "input"))
      (node (ref "IC3") (pin "8") (pinfunction "4D_8") (pintype "input"))
      (node (ref "IC4") (pin "8") (pinfunction "4D_8") (pintype "input"))
      (node (ref "IC5") (pin "8") (pinfunction "4D_8") (pintype "input"))
      (node (ref "IC6") (pin "8") (pinfunction "4D_8") (pintype "input"))
      (node (ref "IC7") (pin "8") (pinfunction "4D_8") (pintype "input"))
      (node (ref "IC8") (pin "8") (pinfunction "4D_8") (pintype "input"))
    )
    (net (code "159") (name "PIA-A4") (class "Default")
      (node (ref "CORE-IO") (pin "5") (pinfunction "5_5") (pintype "passive"))
      (node (ref "IC1") (pin "13") (pinfunction "5D_13") (pintype "input"))
      (node (ref "IC11") (pin "12") (pinfunction "5Q_12") (pintype "tri_state"))
      (node (ref "IC12") (pin "12") (pinfunction "5Q_12") (pintype "tri_state"))
      (node (ref "IC13") (pin "12") (pinfunction "5Q_12") (pintype "tri_state"))
      (node (ref "IC14") (pin "12") (pinfunction "5Q_12") (pintype "tri_state"))
      (node (ref "IC15") (pin "12") (pinfunction "5Q_12") (pintype "tri_state"))
      (node (ref "IC16") (pin "12") (pinfunction "5Q_12") (pintype "tri_state"))
      (node (ref "IC17") (pin "12") (pinfunction "5Q_12") (pintype "tri_state"))
      (node (ref "IC18") (pin "12") (pinfunction "5Q_12") (pintype "tri_state"))
      (node (ref "IC2") (pin "13") (pinfunction "5D_13") (pintype "input"))
      (node (ref "IC3") (pin "13") (pinfunction "5D_13") (pintype "input"))
      (node (ref "IC4") (pin "13") (pinfunction "5D_13") (pintype "input"))
      (node (ref "IC5") (pin "13") (pinfunction "5D_13") (pintype "input"))
      (node (ref "IC6") (pin "13") (pinfunction "5D_13") (pintype "input"))
      (node (ref "IC7") (pin "13") (pinfunction "5D_13") (pintype "input"))
      (node (ref "IC8") (pin "13") (pinfunction "5D_13") (pintype "input"))
    )
    (net (code "160") (name "PIA-A5") (class "Default")
      (node (ref "CORE-IO") (pin "6") (pinfunction "6_6") (pintype "passive"))
      (node (ref "IC1") (pin "14") (pinfunction "6D_14") (pintype "input"))
      (node (ref "IC11") (pin "15") (pinfunction "6Q_15") (pintype "tri_state"))
      (node (ref "IC12") (pin "15") (pinfunction "6Q_15") (pintype "tri_state"))
      (node (ref "IC13") (pin "15") (pinfunction "6Q_15") (pintype "tri_state"))
      (node (ref "IC14") (pin "15") (pinfunction "6Q_15") (pintype "tri_state"))
      (node (ref "IC15") (pin "15") (pinfunction "6Q_15") (pintype "tri_state"))
      (node (ref "IC16") (pin "15") (pinfunction "6Q_15") (pintype "tri_state"))
      (node (ref "IC17") (pin "15") (pinfunction "6Q_15") (pintype "tri_state"))
      (node (ref "IC18") (pin "15") (pinfunction "6Q_15") (pintype "tri_state"))
      (node (ref "IC2") (pin "14") (pinfunction "6D_14") (pintype "input"))
      (node (ref "IC3") (pin "14") (pinfunction "6D_14") (pintype "input"))
      (node (ref "IC4") (pin "14") (pinfunction "6D_14") (pintype "input"))
      (node (ref "IC5") (pin "14") (pinfunction "6D_14") (pintype "input"))
      (node (ref "IC6") (pin "14") (pinfunction "6D_14") (pintype "input"))
      (node (ref "IC7") (pin "14") (pinfunction "6D_14") (pintype "input"))
      (node (ref "IC8") (pin "14") (pinfunction "6D_14") (pintype "input"))
    )
    (net (code "161") (name "PIA-A6") (class "Default")
      (node (ref "CORE-IO") (pin "7") (pinfunction "7_7") (pintype "passive"))
      (node (ref "IC1") (pin "17") (pinfunction "7D_17") (pintype "input"))
      (node (ref "IC11") (pin "16") (pinfunction "7Q_16") (pintype "tri_state"))
      (node (ref "IC12") (pin "16") (pinfunction "7Q_16") (pintype "tri_state"))
      (node (ref "IC13") (pin "16") (pinfunction "7Q_16") (pintype "tri_state"))
      (node (ref "IC14") (pin "16") (pinfunction "7Q_16") (pintype "tri_state"))
      (node (ref "IC15") (pin "16") (pinfunction "7Q_16") (pintype "tri_state"))
      (node (ref "IC16") (pin "16") (pinfunction "7Q_16") (pintype "tri_state"))
      (node (ref "IC17") (pin "16") (pinfunction "7Q_16") (pintype "tri_state"))
      (node (ref "IC18") (pin "16") (pinfunction "7Q_16") (pintype "tri_state"))
      (node (ref "IC2") (pin "17") (pinfunction "7D_17") (pintype "input"))
      (node (ref "IC3") (pin "17") (pinfunction "7D_17") (pintype "input"))
      (node (ref "IC4") (pin "17") (pinfunction "7D_17") (pintype "input"))
      (node (ref "IC5") (pin "17") (pinfunction "7D_17") (pintype "input"))
      (node (ref "IC6") (pin "17") (pinfunction "7D_17") (pintype "input"))
      (node (ref "IC7") (pin "17") (pinfunction "7D_17") (pintype "input"))
      (node (ref "IC8") (pin "17") (pinfunction "7D_17") (pintype "input"))
    )
    (net (code "162") (name "PIA-A7") (class "Default")
      (node (ref "CORE-IO") (pin "8") (pinfunction "8_8") (pintype "passive"))
      (node (ref "IC1") (pin "18") (pinfunction "8D_18") (pintype "input"))
      (node (ref "IC11") (pin "19") (pinfunction "8Q_19") (pintype "tri_state"))
      (node (ref "IC12") (pin "19") (pinfunction "8Q_19") (pintype "tri_state"))
      (node (ref "IC13") (pin "19") (pinfunction "8Q_19") (pintype "tri_state"))
      (node (ref "IC14") (pin "19") (pinfunction "8Q_19") (pintype "tri_state"))
      (node (ref "IC15") (pin "19") (pinfunction "8Q_19") (pintype "tri_state"))
      (node (ref "IC16") (pin "19") (pinfunction "8Q_19") (pintype "tri_state"))
      (node (ref "IC17") (pin "19") (pinfunction "8Q_19") (pintype "tri_state"))
      (node (ref "IC18") (pin "19") (pinfunction "8Q_19") (pintype "tri_state"))
      (node (ref "IC2") (pin "18") (pinfunction "8D_18") (pintype "input"))
      (node (ref "IC3") (pin "18") (pinfunction "8D_18") (pintype "input"))
      (node (ref "IC4") (pin "18") (pinfunction "8D_18") (pintype "input"))
      (node (ref "IC5") (pin "18") (pinfunction "8D_18") (pintype "input"))
      (node (ref "IC6") (pin "18") (pinfunction "8D_18") (pintype "input"))
      (node (ref "IC7") (pin "18") (pinfunction "8D_18") (pintype "input"))
      (node (ref "IC8") (pin "18") (pinfunction "8D_18") (pintype "input"))
    )
    (net (code "163") (name "PIA-B0") (class "Default")
      (node (ref "CORE-IO") (pin "13") (pinfunction "13_13") (pintype "passive"))
      (node (ref "IC10") (pin "1") (pinfunction "A_1") (pintype "input"))
      (node (ref "IC9") (pin "1") (pinfunction "A_1") (pintype "input"))
    )
    (net (code "164") (name "PIA-B1") (class "Default")
      (node (ref "CORE-IO") (pin "14") (pinfunction "14_14") (pintype "passive"))
      (node (ref "IC10") (pin "2") (pinfunction "B_2") (pintype "input"))
      (node (ref "IC9") (pin "2") (pinfunction "B_2") (pintype "input"))
    )
    (net (code "165") (name "PIA-B2") (class "Default")
      (node (ref "CORE-IO") (pin "15") (pinfunction "15_15") (pintype "passive"))
      (node (ref "IC10") (pin "3") (pinfunction "C_3") (pintype "input"))
      (node (ref "IC9") (pin "3") (pinfunction "C_3") (pintype "input"))
    )
    (net (code "166") (name "PIA-B3") (class "Default")
      (node (ref "CORE-IO") (pin "16") (pinfunction "16_16") (pintype "passive"))
      (node (ref "IC19") (pin "1") (pinfunction "A_1") (pintype "input"))
    )
    (net (code "167") (name "PIA-B4") (class "Default")
      (node (ref "CORE-IO") (pin "17") (pinfunction "17_17") (pintype "passive"))
      (node (ref "IC19") (pin "2") (pinfunction "B_2") (pintype "input"))
    )
    (net (code "168") (name "PIA-B5") (class "Default")
      (node (ref "CORE-IO") (pin "18") (pinfunction "18_18") (pintype "passive"))
      (node (ref "IC19") (pin "3") (pinfunction "C_3") (pintype "input"))
    )
    (net (code "169") (name "PIA-B6") (class "Default")
      (node (ref "CORE-IO") (pin "19") (pinfunction "19_19") (pintype "passive"))
      (node (ref "IC10") (pin "6") (pinfunction "G1_6") (pintype "input"))
      (node (ref "IC9") (pin "4") (pinfunction "G2A_4") (pintype "input"))
    )
    (net (code "170") (name "PIA-B7") (class "Default")
      (node (ref "CORE-IO") (pin "20") (pinfunction "20_20") (pintype "passive"))
      (node (ref "DEVSEL") (pin "2") (pinfunction "2_2") (pintype "passive"))
      (node (ref "IC19") (pin "5") (pinfunction "G2B_5") (pintype "input"))
    )
    (net (code "171") (name "VCC") (class "Default")
      (node (ref "BYP1") (pin "1") (pinfunction "1_1") (pintype "passive"))
      (node (ref "BYP10") (pin "1") (pinfunction "1_1") (pintype "passive"))
      (node (ref "BYP11") (pin "1") (pinfunction "1_1") (pintype "passive"))
      (node (ref "BYP12") (pin "1") (pinfunction "1_1") (pintype "passive"))
      (node (ref "BYP13") (pin "1") (pinfunction "1_1") (pintype "passive"))
      (node (ref "BYP14") (pin "1") (pinfunction "1_1") (pintype "passive"))
      (node (ref "BYP15") (pin "1") (pinfunction "1_1") (pintype "passive"))
      (node (ref "BYP16") (pin "1") (pinfunction "1_1") (pintype "passive"))
      (node (ref "BYP17") (pin "1") (pinfunction "1_1") (pintype "passive"))
      (node (ref "BYP18") (pin "1") (pinfunction "1_1") (pintype "passive"))
      (node (ref "BYP19") (pin "1") (pinfunction "1_1") (pintype "passive"))
      (node (ref "BYP2") (pin "1") (pinfunction "1_1") (pintype "passive"))
      (node (ref "BYP20") (pin "1") (pinfunction "1_1") (pintype "passive"))
      (node (ref "BYP3") (pin "1") (pinfunction "1_1") (pintype "passive"))
      (node (ref "BYP4") (pin "1") (pinfunction "1_1") (pintype "passive"))
      (node (ref "BYP5") (pin "1") (pinfunction "1_1") (pintype "passive"))
      (node (ref "BYP6") (pin "1") (pinfunction "1_1") (pintype "passive"))
      (node (ref "BYP7") (pin "1") (pinfunction "1_1") (pintype "passive"))
      (node (ref "BYP8") (pin "1") (pinfunction "1_1") (pintype "passive"))
      (node (ref "BYP9") (pin "1") (pinfunction "1_1") (pintype "passive"))
      (node (ref "CORE-IO") (pin "12") (pinfunction "12_12") (pintype "passive"))
      (node (ref "CORE-IO") (pin "9") (pinfunction "9_9") (pintype "passive"))
      (node (ref "IC11") (pin "11") (pinfunction "ENC_11") (pintype "input"))
      (node (ref "IC12") (pin "11") (pinfunction "ENC_11") (pintype "input"))
      (node (ref "IC13") (pin "11") (pinfunction "ENC_11") (pintype "input"))
      (node (ref "IC14") (pin "11") (pinfunction "ENC_11") (pintype "input"))
      (node (ref "IC15") (pin "11") (pinfunction "ENC_11") (pintype "input"))
      (node (ref "IC16") (pin "11") (pinfunction "ENC_11") (pintype "input"))
      (node (ref "IC17") (pin "11") (pinfunction "ENC_11") (pintype "input"))
      (node (ref "IC18") (pin "11") (pinfunction "ENC_11") (pintype "input"))
      (node (ref "IC19") (pin "6") (pinfunction "G1_6") (pintype "input"))
      (node (ref "IC9") (pin "6") (pinfunction "G1_6") (pintype "input"))
      (node (ref "JP2") (pin "2") (pinfunction "2_2") (pintype "passive"))
    )
  )
)
